# Sec_Gate_Driver.net
KiCad netlist of a schematic drawn in Altium Designer
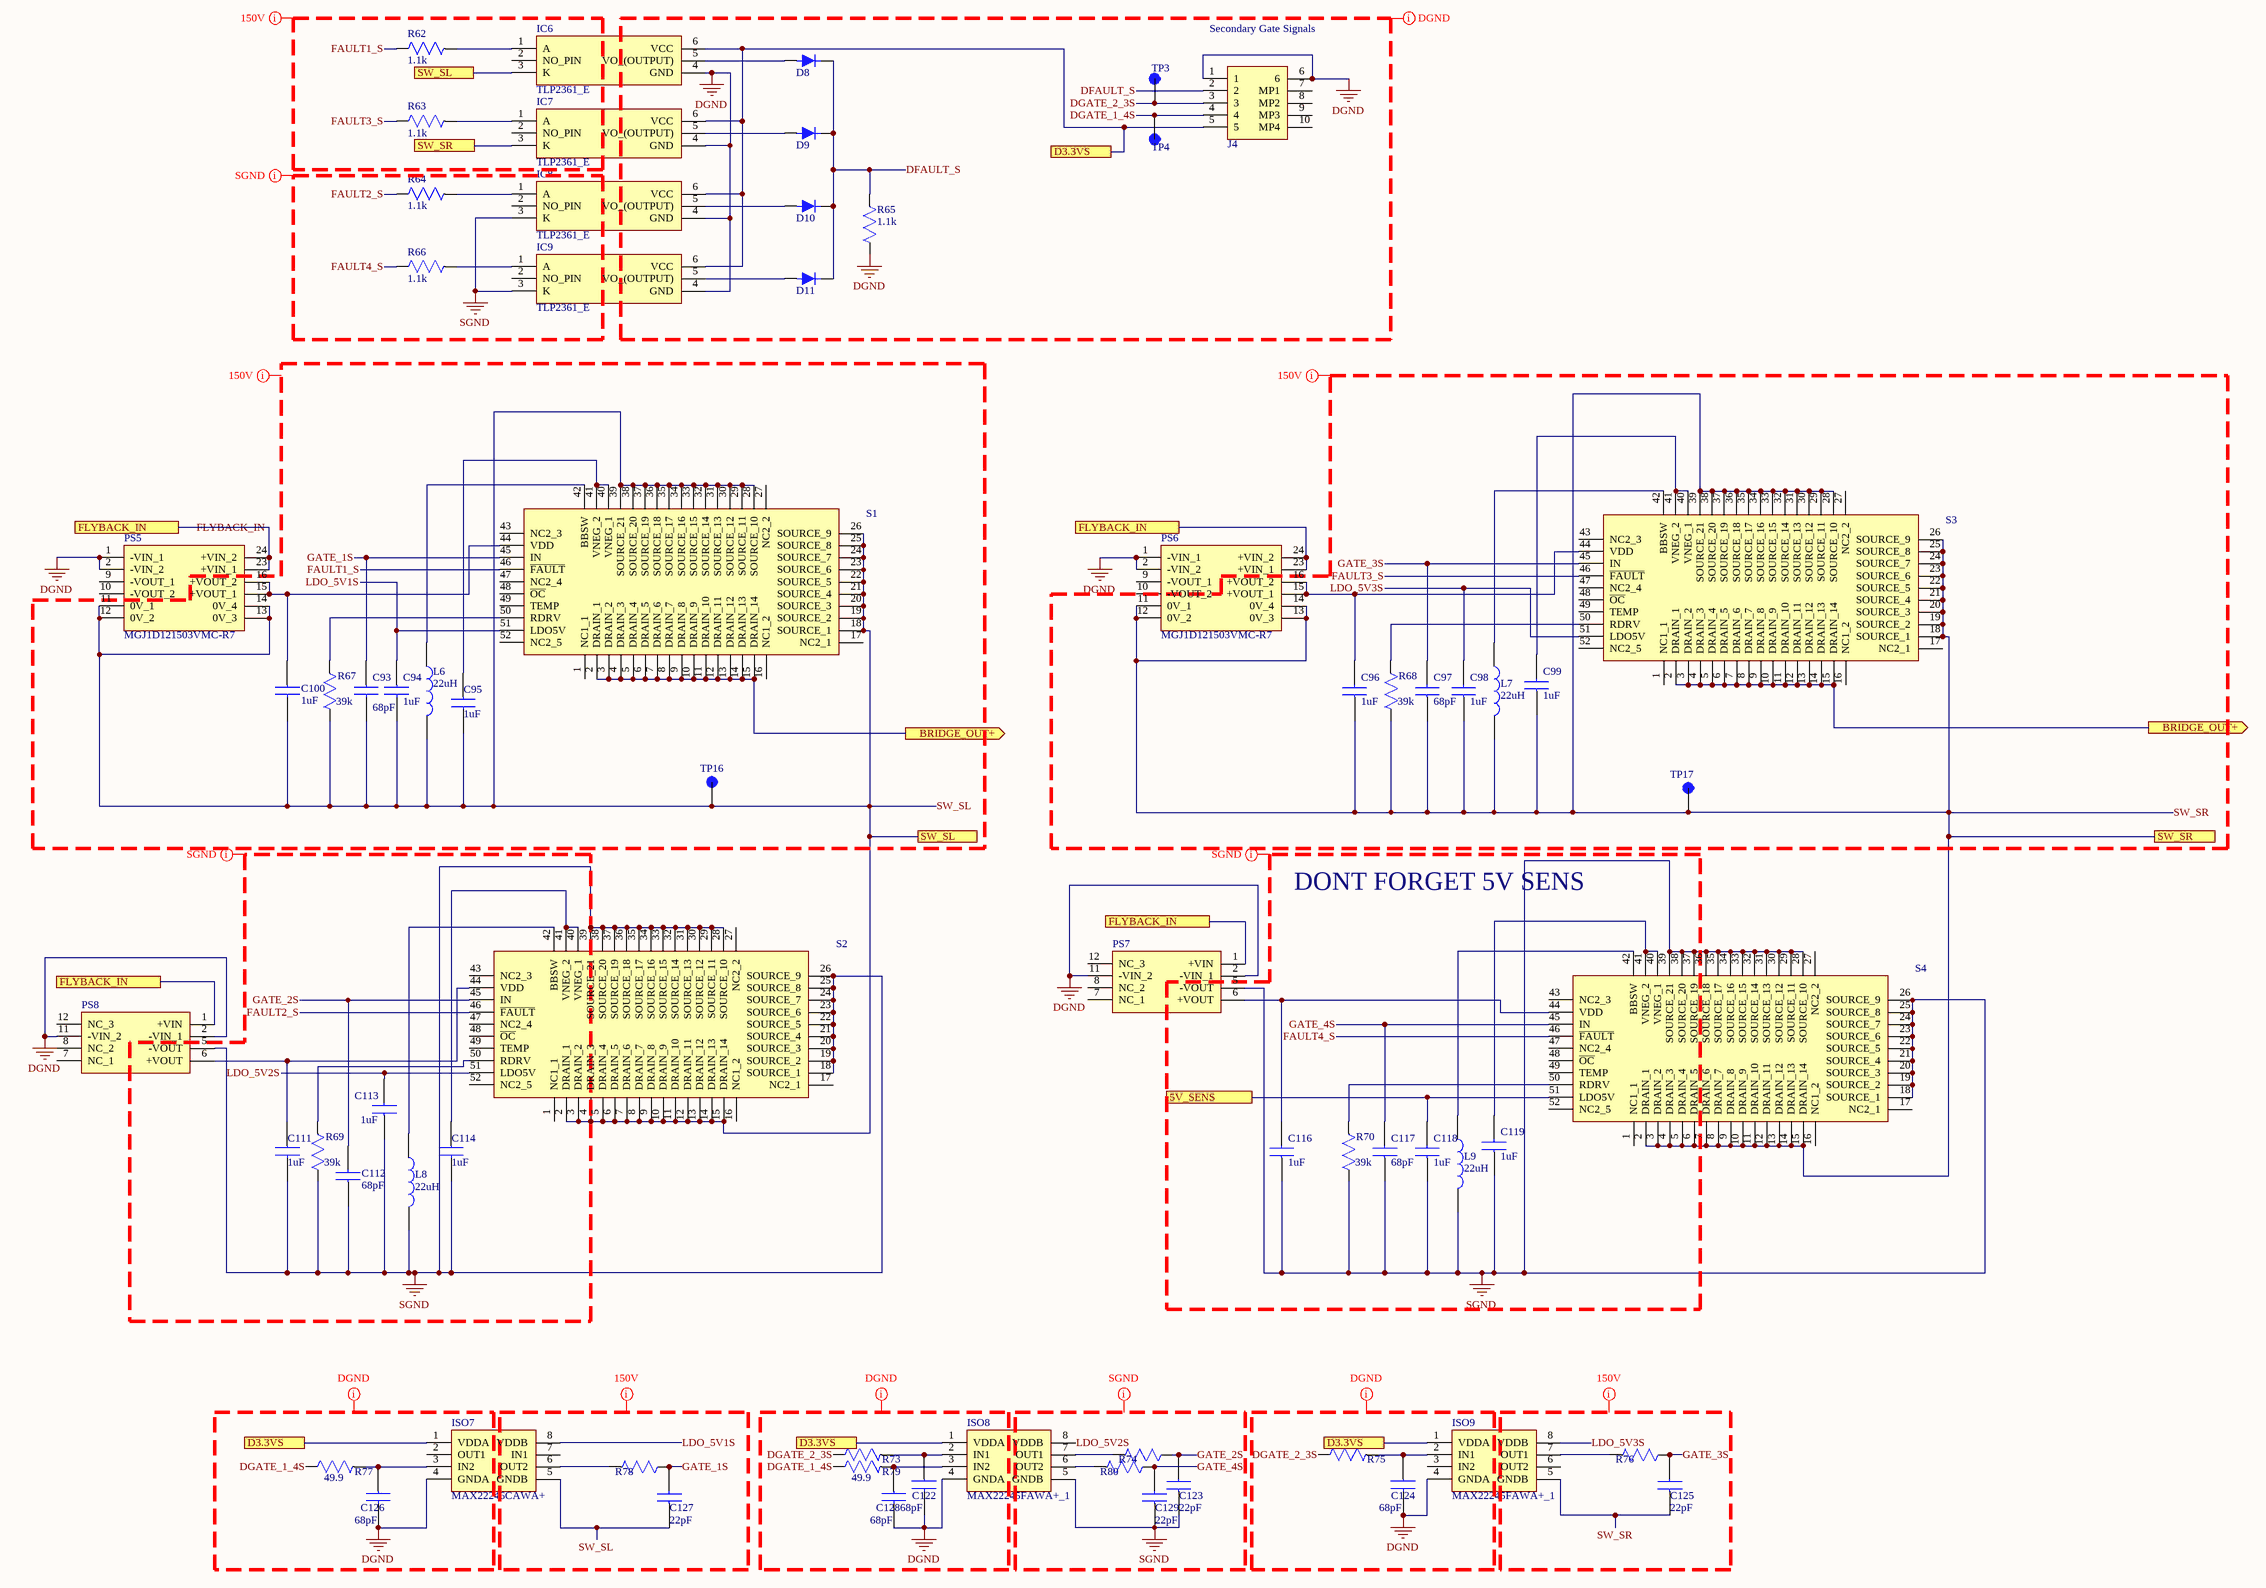
[diagram p0: Sec_Gate_Driver.SchDoc]

(export (version "E")
  (design (tool "Eeschema 10.0.6"))
  (components
    (comp (ref "C93")
      (value "68pF")
      (footprint "C0805")
      (description "Capacitor")
      (fields
        (field (name "MANUFACTURER_PART_NUMBER") "C0805C680J5GACTU")
        (field (name "MOUSER PART NUMBER") "80-C0805C680J5G")
      )
      (libsource (lib "PriGateDriver") (part "C0805C680J5GACTU"))
    )
    (comp (ref "C94")
      (value "1uF")
      (footprint "CAPC2012X135N")
      (description "Capacitor")
      (fields
        (field (name "MANUFACTURER_PART_NUMBER") "CL21B105KBFNNNE")
        (field (name "MOUSER PART NUMBER") "187-CL21B105KBFNNNE")
      )
      (libsource (lib "SecGateDriver") (part "CL21B105KBFNNNE"))
    )
    (comp (ref "C95")
      (value "1uF")
      (footprint "CAPC2012X135N")
      (description "Capacitor")
      (fields
        (field (name "MANUFACTURER_PART_NUMBER") "CL21B105KBFNNNE")
        (field (name "MOUSER PART NUMBER") "187-CL21B105KBFNNNE")
      )
      (libsource (lib "SecGateDriver") (part "CL21B105KBFNNNE"))
    )
    (comp (ref "C96")
      (value "1uF")
      (footprint "CAPC2012X70N")
      (description "CAP CER 1UF 50V X7R 0805")
      (fields
        (field (name "MANUFACTURER_PART_NUMBER") "CL21B105KBFNNNE")
        (field (name "MOUSER PART NUMBER") "187-CL21B105KBFNNNE")
      )
      (libsource (lib "SecGateDriver") (part "CL21B105KBFNNNE"))
    )
    (comp (ref "C97")
      (value "68pF")
      (footprint "C0805")
      (description "CAP CER 68PF 50V C0G/NP0 0805")
      (fields
        (field (name "MANUFACTURER_PART_NUMBER") "C0805C680J5GACTU")
        (field (name "MOUSER PART NUMBER") "80-C0805C680J5G")
      )
      (libsource (lib "SecGateDriver") (part "C0805C680J5GACTU"))
    )
    (comp (ref "C98")
      (value "1uF")
      (footprint "CAPC2012X135N")
      (description "CAP CER 1UF 50V X7R 0805")
      (fields
        (field (name "MANUFACTURER_PART_NUMBER") "CL21B105KBFNNNE")
        (field (name "MOUSER PART NUMBER") "187-CL21B105KBFNNNE")
      )
      (libsource (lib "SecGateDriver") (part "CL21B105KBFNNNE"))
    )
    (comp (ref "C99")
      (value "1uF")
      (footprint "CAPC2012X135N")
      (description "CAP CER 1UF 50V X7R 0805")
      (fields
        (field (name "MANUFACTURER_PART_NUMBER") "CL21B105KBFNNNE")
        (field (name "MOUSER PART NUMBER") "187-CL21B105KBFNNNE")
      )
      (libsource (lib "SecGateDriver") (part "CL21B105KBFNNNE"))
    )
    (comp (ref "C100")
      (value "1uF")
      (footprint "CAPC2012X135N")
      (description "Capacitor")
      (fields
        (field (name "MANUFACTURER_PART_NUMBER") "CL21B105KBFNNNE")
        (field (name "MOUSER PART NUMBER") "187-CL21B105KBFNNNE")
      )
      (libsource (lib "SecGateDriver") (part "CL21B105KBFNNNE"))
    )
    (comp (ref "C111")
      (value "1uF")
      (footprint "CAPC2012X135N")
      (description "Capacitor")
      (fields
        (field (name "MANUFACTURER_PART_NUMBER") "CL21B105KBFNNNE")
        (field (name "MOUSER PART NUMBER") "187-CL21B105KBFNNNE")
      )
      (libsource (lib "SecGateDriver") (part "CL21B105KBFNNNE"))
    )
    (comp (ref "C112")
      (value "68pF")
      (footprint "C0805")
      (description "CAP CER 68PF 50V C0G/NP0 0805")
      (fields
        (field (name "MANUFACTURER_PART_NUMBER") "C0805C680J5GACTU")
        (field (name "MOUSER PART NUMBER") "80-C0805C680J5G")
      )
      (libsource (lib "Sec_Gate_Driver") (part "C0805C680J5GACTU_1"))
    )
    (comp (ref "C113")
      (value "1uF")
      (footprint "CAPC2012X70N")
      (description "CAP CER 1UF 50V X7R 0805")
      (fields
        (field (name "MANUFACTURER_PART_NUMBER") "CL21B105KBFNNNE")
        (field (name "MOUSER PART NUMBER") "187-CL21B105KBFNNNE")
      )
      (libsource (lib "Sec_Gate_Driver") (part "CL21B105KBFNNNE"))
    )
    (comp (ref "C114")
      (value "1uF")
      (footprint "CAPC2012X135N")
      (description "Capacitor")
      (fields
        (field (name "MANUFACTURER_PART_NUMBER") "CL21B105KBFNNNE")
        (field (name "MOUSER PART NUMBER") "187-CL21B105KBFNNNE")
      )
      (libsource (lib "SecGateDriver") (part "CL21B105KBFNNNE"))
    )
    (comp (ref "C116")
      (value "1uF")
      (footprint "CAPC2012X70N")
      (description "CAP CER 1UF 50V X7R 0805")
      (fields
        (field (name "MANUFACTURER_PART_NUMBER") "CL21B105KBFNNNE")
        (field (name "MOUSER PART NUMBER") "187-CL21B105KBFNNNE")
      )
      (libsource (lib "SecGateDriver") (part "CL21B105KBFNNNE"))
    )
    (comp (ref "C117")
      (value "68pF")
      (footprint "C0805")
      (description "CAP CER 68PF 50V C0G/NP0 0805")
      (fields
        (field (name "MANUFACTURER_PART_NUMBER") "C0805C680J5GACTU")
        (field (name "MOUSER PART NUMBER") "80-C0805C680J5G")
      )
      (libsource (lib "SecGateDriver") (part "C0805C680J5GACTU"))
    )
    (comp (ref "C118")
      (value "1uF")
      (footprint "CAPC2012X70N")
      (description "CAP CER 1UF 50V X7R 0805")
      (fields
        (field (name "MANUFACTURER_PART_NUMBER") "CL21B105KBFNNNE")
        (field (name "MOUSER PART NUMBER") "187-CL21B105KBFNNNE")
      )
      (libsource (lib "SecGateDriver") (part "CL21B105KBFNNNE"))
    )
    (comp (ref "C119")
      (value "1uF")
      (footprint "CAPC2012X70N")
      (description "CAP CER 1UF 50V X7R 0805")
      (fields
        (field (name "MANUFACTURER_PART_NUMBER") "CL21B105KBFNNNE")
        (field (name "MOUSER PART NUMBER") "187-CL21B105KBFNNNE")
      )
      (libsource (lib "SecGateDriver") (part "CL21B105KBFNNNE"))
    )
    (comp (ref "C122")
      (value "68pF")
      (footprint "C0805")
      (description "CAP CER 68PF 50V C0G/NP0 0805")
      (fields
        (field (name "MANUFACTURER_PART_NUMBER") "C0805C680J5GACTU")
        (field (name "MOUSER PART NUMBER") "80-C0805C680J5G")
      )
      (libsource (lib "Sec_Gate_Driver") (part "C0805C680J5GACTU_1"))
    )
    (comp (ref "C123")
      (value "22pF")
      (footprint "C0805")
      (description "CAP CER 22PF 100V C0G/NP0 0805")
      (fields
        (field (name "MANUFACTURER_PART_NUMBER") "C0805C220J1GACTU")
        (field (name "MOUSER PART NUMBER") "80-C0805C220J1G")
      )
      (libsource (lib "Sec_Gate_Driver") (part "C0805C220J1GACTU"))
    )
    (comp (ref "C124")
      (value "68pF")
      (footprint "C0805")
      (description "CAP CER 68PF 50V C0G/NP0 0805")
      (fields
        (field (name "MANUFACTURER_PART_NUMBER") "C0805C680J5GACTU")
        (field (name "MOUSER PART NUMBER") "80-C0805C680J5G")
      )
      (libsource (lib "Sec_Gate_Driver") (part "C0805C680J5GACTU_1"))
    )
    (comp (ref "C125")
      (value "22pF")
      (footprint "C0805")
      (description "CAP CER 22PF 100V C0G/NP0 0805")
      (fields
        (field (name "MANUFACTURER_PART_NUMBER") "C0805C220J1GACTU")
        (field (name "MOUSER PART NUMBER") "80-C0805C220J1G")
      )
      (libsource (lib "Sec_Gate_Driver") (part "C0805C220J1GACTU"))
    )
    (comp (ref "C126")
      (value "68pF")
      (footprint "C0805")
      (description "CAP CER 68PF 50V C0G/NP0 0805")
      (fields
        (field (name "MANUFACTURER_PART_NUMBER") "C0805C680J5GACTU")
        (field (name "MOUSER PART NUMBER") "80-C0805C680J5G")
      )
      (libsource (lib "Sec_Gate_Driver") (part "C0805C680J5GACTU_1"))
    )
    (comp (ref "C127")
      (value "22pF")
      (footprint "C0805")
      (description "CAP CER 22PF 100V C0G/NP0 0805")
      (fields
        (field (name "MANUFACTURER_PART_NUMBER") "C0805C220J1GACTU")
        (field (name "MOUSER PART NUMBER") "80-C0805C220J1G")
      )
      (libsource (lib "Sec_Gate_Driver") (part "C0805C220J1GACTU"))
    )
    (comp (ref "C128")
      (value "68pF")
      (footprint "C0805")
      (description "CAP CER 68PF 50V C0G/NP0 0805")
      (fields
        (field (name "MANUFACTURER_PART_NUMBER") "C0805C680J5GACTU")
        (field (name "MOUSER PART NUMBER") "80-C0805C680J5G")
      )
      (libsource (lib "Sec_Gate_Driver") (part "C0805C680J5GACTU_1"))
    )
    (comp (ref "C129")
      (value "22pF")
      (footprint "C0805")
      (description "CAP CER 22PF 100V C0G/NP0 0805")
      (fields
        (field (name "MANUFACTURER_PART_NUMBER") "C0805C220J1GACTU")
        (field (name "MOUSER PART NUMBER") "80-C0805C220J1G")
      )
      (libsource (lib "Sec_Gate_Driver") (part "C0805C220J1GACTU"))
    )
    (comp (ref "D8")
      (value "CUS520,H3F")
      (footprint "SOD2513X115N")
      (description "DIODE SCHOTTKY 30V 200MA USC")
      (fields
        (field (name "MANUFACTURER_PART_NUMBER") "MMSD4148T1G")
        (field (name "MOUSER PART NUMBER") "863-MMSD4148T1G")
      )
      (libsource (lib "Sec_Gate_Driver") (part "CUS520,H3F"))
    )
    (comp (ref "D9")
      (value "CUS520,H3F")
      (footprint "SOD2513X115N")
      (description "DIODE SCHOTTKY 30V 200MA USC")
      (fields
        (field (name "MANUFACTURER_PART_NUMBER") "MMSD4148T1G")
        (field (name "MOUSER PART NUMBER") "863-MMSD4148T1G")
      )
      (libsource (lib "Sec_Gate_Driver") (part "CUS520,H3F"))
    )
    (comp (ref "D10")
      (value "CUS520,H3F")
      (footprint "SOD2513X115N")
      (description "DIODE SCHOTTKY 30V 200MA USC")
      (fields
        (field (name "MANUFACTURER_PART_NUMBER") "MMSD4148T1G")
        (field (name "MOUSER PART NUMBER") "863-MMSD4148T1G")
      )
      (libsource (lib "Sec_Gate_Driver") (part "CUS520,H3F"))
    )
    (comp (ref "D11")
      (value "CUS520,H3F")
      (footprint "SOD2513X115N")
      (description "DIODE SCHOTTKY 30V 200MA USC")
      (fields
        (field (name "MANUFACTURER_PART_NUMBER") "MMSD4148T1G")
        (field (name "MOUSER PART NUMBER") "863-MMSD4148T1G")
      )
      (libsource (lib "Sec_Gate_Driver") (part "CUS520,H3F"))
    )
    (comp (ref "IC6")
      (value "TLP2361_E")
      (footprint "SOIC127P700X230-6N")
      (description "Integrated Circuit")
      (fields
        (field (name "MANUFACTURER_PART_NUMBER") "TLP2361(E")
        (field (name "MOUSER PART NUMBER") "757-TLP2361(E")
      )
      (libsource (lib "Sec_Gate_Driver") (part "TLP2361_E"))
    )
    (comp (ref "IC7")
      (value "TLP2361_E")
      (footprint "SOIC127P700X230-6N")
      (description "Integrated Circuit")
      (fields
        (field (name "MANUFACTURER_PART_NUMBER") "TLP2361(E")
        (field (name "MOUSER PART NUMBER") "757-TLP2361(E")
      )
      (libsource (lib "Sec_Gate_Driver") (part "TLP2361_E"))
    )
    (comp (ref "IC8")
      (value "TLP2361_E")
      (footprint "SOIC127P700X230-6N")
      (description "Integrated Circuit")
      (fields
        (field (name "MANUFACTURER_PART_NUMBER") "TLP2361(E")
        (field (name "MOUSER PART NUMBER") "757-TLP2361(E")
      )
      (libsource (lib "Sec_Gate_Driver") (part "TLP2361_E"))
    )
    (comp (ref "IC9")
      (value "TLP2361_E")
      (footprint "SOIC127P700X230-6N")
      (description "Integrated Circuit")
      (fields
        (field (name "MANUFACTURER_PART_NUMBER") "TLP2361(E")
        (field (name "MOUSER PART NUMBER") "757-TLP2361(E")
      )
      (libsource (lib "Sec_Gate_Driver") (part "TLP2361_E"))
    )
    (comp (ref "ISO7")
      (value "MAX22246CAWA+")
      (footprint "SOIC127P1031X265-8N")
      (description "DG ISO 5KV 2CH CAN/RS232 8-SOIC")
      (fields (field (name "MOUSER PART NUMBER") "700-MAX22246CAWA+"))
      (libsource (lib "Sec_Gate_Driver") (part "MAX22246CAWA+"))
    )
    (comp (ref "ISO8")
      (value "MAX22245FAWA+_1")
      (footprint "SOIC127P1031X265-8N")
      (description "DG ISO 5KV 2CH CAN/RS232 8-SOIC")
      (fields (field (name "MANUFACTURER_PART_NUMBER") "MAX22245FAWA+"))
      (libsource (lib "Sec_Gate_Driver") (part "MAX22245FAWA+_1"))
    )
    (comp (ref "ISO9")
      (value "MAX22245FAWA+_1")
      (footprint "SOIC127P1031X265-8N")
      (description "DG ISO 5KV 2CH CAN/RS232 8-SOIC")
      (fields (field (name "MANUFACTURER_PART_NUMBER") "MAX22245FAWA+"))
      (libsource (lib "Sec_Gate_Driver") (part "MAX22245FAWA+_1"))
    )
    (comp (ref "J4")
      (value "0527450696")
      (footprint "0527450696")
      (description "CONN FFC FPC TOP 6POS 0.5MM R/A")
      (libsource (lib "Sec_Gate_Driver") (part "0527450696"))
    )
    (comp (ref "L6")
      (value "22uH")
      (footprint "LQM21DN220N00L")
      (description "Inductor")
      (fields
        (field (name "MANUFACTURER_PART_NUMBER") "LQM21DH220M70L")
        (field (name "MOUSER PART NUMBER") "81-LQM21DH220M70L")
      )
      (libsource (lib "SecGateDriver") (part "LQM21DH220M70L"))
    )
    (comp (ref "L7")
      (value "22uH")
      (footprint "LQM21DN220N00L")
      (description "FIXED IND 22UH 220MA 1.625OHM SM")
      (fields
        (field (name "MANUFACTURER_PART_NUMBER") "LQM21DH220M70L")
        (field (name "MOUSER PART NUMBER") "81-LQM21DH220M70L")
      )
      (libsource (lib "SecGateDriver") (part "LQM21DH220M70L"))
    )
    (comp (ref "L8")
      (value "22uH")
      (footprint "LQM21DN220N00L")
      (description "Inductor")
      (fields
        (field (name "MANUFACTURER_PART_NUMBER") "LQM21DH220M70L")
        (field (name "MOUSER PART NUMBER") "81-LQM21DH220M70L")
      )
      (libsource (lib "SecGateDriver") (part "LQM21DH220M70L"))
    )
    (comp (ref "L9")
      (value "22uH")
      (footprint "LQM21DN220N00L")
      (description "FIXED IND 22UH 220MA 1.625OHM SM")
      (fields
        (field (name "MANUFACTURER_PART_NUMBER") "LQM21DH220M70L")
        (field (name "MOUSER PART NUMBER") "81-LQM21DH220M70L")
      )
      (libsource (lib "SecGateDriver") (part "LQM21DH220M70L"))
    )
    (comp (ref "PS5")
      (value "MGJ1D121503VMC-R7")
      (footprint "MGJ1D121503VMCR7")
      (description "DC DC CONVERTER 15V -3V 1W")
      (fields (field (name "MOUSER PART NUMBER") "580-MGJ1D121503VMCR7"))
      (libsource (lib "SecGateDriver") (part "MGJ1D121503VMC-R7"))
    )
    (comp (ref "PS6")
      (value "MGJ1D121503VMC-R7")
      (footprint "MGJ1D121503VMCR7")
      (description "DC DC CONVERTER 15V -3V 1W")
      (fields (field (name "MOUSER PART NUMBER") "580-MGJ1D121503VMCR7"))
      (libsource (lib "SecGateDriver") (part "MGJ1D121503VMC-R7"))
    )
    (comp (ref "PS7")
      (value "NXJ2S1212MC-R7")
      (footprint "NXJ2S1212MCR7")
      (description "DC DC CONVERTER 12V 2W")
      (fields (field (name "MOUSER PART NUMBER") "580-NXJ2S1212MC-R7"))
      (libsource (lib "Sec_Gate_Driver") (part "NXJ2S1212MC-R7"))
    )
    (comp (ref "PS8")
      (value "NXJ2S1212MC-R7")
      (footprint "NXJ2S1212MCR7")
      (description "DC DC CONVERTER 12V 2W")
      (fields (field (name "MOUSER PART NUMBER") "580-NXJ2S1212MC-R7"))
      (libsource (lib "SecGateDriver") (part "NXJ2S1212MC-R7"))
    )
    (comp (ref "R62")
      (value "1.1k")
      (footprint "RESC2012X60N")
      (description "RES 1.1K OHM 5% 1/8W 0805")
      (fields
        (field (name "MANUFACTURER_PART_NUMBER") "ERJ-PB6B1002V")
        (field (name "MOUSER PART NUMBER") "667-ERJ-PB6B1002V")
      )
      (libsource (lib "Sec_Gate_Driver") (part "RMCF0805JT1K10"))
    )
    (comp (ref "R63")
      (value "1.1k")
      (footprint "RESC2012X60N")
      (description "RES 1.1K OHM 5% 1/8W 0805")
      (fields
        (field (name "MANUFACTURER_PART_NUMBER") "ERJ-PB6B1002V")
        (field (name "MOUSER PART NUMBER") "667-ERJ-PB6B1002V")
      )
      (libsource (lib "Sec_Gate_Driver") (part "RMCF0805JT1K10"))
    )
    (comp (ref "R64")
      (value "1.1k")
      (footprint "RESC2012X60N")
      (description "RES 1.1K OHM 5% 1/8W 0805")
      (fields
        (field (name "MANUFACTURER_PART_NUMBER") "ERJ-PB6B1002V")
        (field (name "MOUSER PART NUMBER") "667-ERJ-PB6B1002V")
      )
      (libsource (lib "Sec_Gate_Driver") (part "RMCF0805JT1K10"))
    )
    (comp (ref "R65")
      (value "1.1k")
      (footprint "RESC2012X60N")
      (description "RES 1.1K OHM 5% 1/8W 0805")
      (fields
        (field (name "MANUFACTURER_PART_NUMBER") "ERJ-PB6B1002V")
        (field (name "MOUSER PART NUMBER") "667-ERJ-PB6B1002V")
      )
      (libsource (lib "Sec_Gate_Driver") (part "RMCF0805JT1K10"))
    )
    (comp (ref "R66")
      (value "1.1k")
      (footprint "RESC2012X60N")
      (description "RES 1.1K OHM 5% 1/8W 0805")
      (fields
        (field (name "MANUFACTURER_PART_NUMBER") "ERJ-PB6B1002V")
        (field (name "MOUSER PART NUMBER") "667-ERJ-PB6B1002V")
      )
      (libsource (lib "Sec_Gate_Driver") (part "RMCF0805JT1K10"))
    )
    (comp (ref "R67")
      (value "39k")
      (footprint "C0805")
      (description "39 kOhms ±0.1% 0.25W, 1/4W Chip Resistor 0805 (2012 Metric) Automotive AEC-Q200 Thick Film")
      (fields (field (name "MANUFACTURER_PART_NUMBER") "RC0603JR0710KL"))
      (libsource (lib "SecGateDriver") (part "ERJ-PB6B3902V"))
    )
    (comp (ref "R68")
      (value "39k")
      (footprint "C0805")
      (description "39 kOhms ±0.1% 0.25W, 1/4W Chip Resistor 0805 (2012 Metric) Automotive AEC-Q200 Thick Film")
      (fields (field (name "MANUFACTURER_PART_NUMBER") "RC0603JR0710KL"))
      (libsource (lib "SecGateDriver") (part "ERJ-PB6B3902V"))
    )
    (comp (ref "R69")
      (value "39k")
      (footprint "ERJP06D1000V")
      (description "39 kOhms ±0.1% 0.25W, 1/4W Chip Resistor 0805 (2012 Metric) Automotive AEC-Q200 Thick Film")
      (fields (field (name "MANUFACTURER_PART_NUMBER") "RC0603JR0710KL"))
      (libsource (lib "SecGateDriver") (part "ERJ-PB6B3902V"))
    )
    (comp (ref "R70")
      (value "39k")
      (footprint "C0805")
      (description "39 kOhms ±0.1% 0.25W, 1/4W Chip Resistor 0805 (2012 Metric) Automotive AEC-Q200 Thick Film")
      (fields (field (name "MANUFACTURER_PART_NUMBER") "RC0603JR0710KL"))
      (libsource (lib "SecGateDriver") (part "ERJ-PB6B3902V"))
    )
    (comp (ref "R73")
      (value "49.9")
      (footprint "RESC2013X84N")
      (description "RES SMD 49.9 OHM 0.1% 1W 0805")
      (fields
        (field (name "MANUFACTURER_PART_NUMBER") "PCAN0805E49R9BST5")
        (field (name "MOUSER PART NUMBER") "71-PCAN0805E49R9BST5")
      )
      (libsource (lib "Sec_Gate_Driver") (part "PCAN0805E49R9BST5"))
    )
    (comp (ref "R74")
      (value "49.9")
      (footprint "RESC2013X84N")
      (description "RES SMD 49.9 OHM 0.1% 1W 0805")
      (fields
        (field (name "MANUFACTURER_PART_NUMBER") "PCAN0805E49R9BST5")
        (field (name "MOUSER PART NUMBER") "71-PCAN0805E49R9BST5")
      )
      (libsource (lib "Sec_Gate_Driver") (part "PCAN0805E49R9BST5"))
    )
    (comp (ref "R75")
      (value "49.9")
      (footprint "RESC2013X84N")
      (description "RES SMD 49.9 OHM 0.1% 1W 0805")
      (fields
        (field (name "MANUFACTURER_PART_NUMBER") "PCAN0805E49R9BST5")
        (field (name "MOUSER PART NUMBER") "71-PCAN0805E49R9BST5")
      )
      (libsource (lib "Sec_Gate_Driver") (part "PCAN0805E49R9BST5"))
    )
    (comp (ref "R76")
      (value "49.9")
      (footprint "RESC2013X84N")
      (description "RES SMD 49.9 OHM 0.1% 1W 0805")
      (fields
        (field (name "MANUFACTURER_PART_NUMBER") "PCAN0805E49R9BST5")
        (field (name "MOUSER PART NUMBER") "71-PCAN0805E49R9BST5")
      )
      (libsource (lib "Sec_Gate_Driver") (part "PCAN0805E49R9BST5"))
    )
    (comp (ref "R77")
      (value "49.9")
      (footprint "RESC2013X84N")
      (description "RES SMD 49.9 OHM 0.1% 1W 0805")
      (fields
        (field (name "MANUFACTURER_PART_NUMBER") "PCAN0805E49R9BST5")
        (field (name "MOUSER PART NUMBER") "71-PCAN0805E49R9BST5")
      )
      (libsource (lib "Sec_Gate_Driver") (part "PCAN0805E49R9BST5"))
    )
    (comp (ref "R78")
      (value "49.9")
      (footprint "RESC2013X84N")
      (description "RES SMD 49.9 OHM 0.1% 1W 0805")
      (fields
        (field (name "MANUFACTURER_PART_NUMBER") "PCAN0805E49R9BST5")
        (field (name "MOUSER PART NUMBER") "71-PCAN0805E49R9BST5")
      )
      (libsource (lib "Sec_Gate_Driver") (part "PCAN0805E49R9BST5"))
    )
    (comp (ref "R79")
      (value "49.9")
      (footprint "RESC2013X84N")
      (description "RES SMD 49.9 OHM 0.1% 1W 0805")
      (fields
        (field (name "MANUFACTURER_PART_NUMBER") "PCAN0805E49R9BST5")
        (field (name "MOUSER PART NUMBER") "71-PCAN0805E49R9BST5")
      )
      (libsource (lib "Sec_Gate_Driver") (part "PCAN0805E49R9BST5"))
    )
    (comp (ref "R80")
      (value "49.9")
      (footprint "RESC2013X84N")
      (description "RES SMD 49.9 OHM 0.1% 1W 0805")
      (fields
        (field (name "MANUFACTURER_PART_NUMBER") "PCAN0805E49R9BST5")
        (field (name "MOUSER PART NUMBER") "71-PCAN0805E49R9BST5")
      )
      (libsource (lib "Sec_Gate_Driver") (part "PCAN0805E49R9BST5"))
    )
    (comp (ref "S1")
      (value "LMG3522R030RQSR")
      (footprint "LMG3522R050RQSR")
      (description "Integrated Circuit")
      (fields
        (field (name "MANUFACTURER_PART_NUMBER") "LMG3522R050RQSR")
        (field (name "MOUSER PART NUMBER") "595-LMG3522R050RQSR")
      )
      (libsource (lib "*") (part "LMG3522R050RQSR"))
    )
    (comp (ref "S2")
      (value "LMG3522R030RQSR")
      (footprint "LMG3522R050RQSR")
      (description "Integrated Circuit")
      (fields
        (field (name "MANUFACTURER_PART_NUMBER") "LMG3522R050RQSR")
        (field (name "MOUSER PART NUMBER") "595-LMG3522R050RQSR")
      )
      (libsource (lib "*") (part "LMG3522R050RQSR"))
    )
    (comp (ref "S3")
      (value "LMG3522R030RQSR")
      (footprint "LMG3522R050RQSR")
      (description "Integrated Circuit")
      (fields
        (field (name "MANUFACTURER_PART_NUMBER") "LMG3522R050RQSR")
        (field (name "MOUSER PART NUMBER") "595-LMG3522R050RQSR")
      )
      (libsource (lib "*") (part "LMG3522R050RQSR"))
    )
    (comp (ref "S4")
      (value "LMG3522R030RQSR")
      (footprint "LMG3522R050RQSR")
      (description "Integrated Circuit")
      (fields
        (field (name "MANUFACTURER_PART_NUMBER") "LMG3522R050RQSR")
        (field (name "MOUSER PART NUMBER") "595-LMG3522R050RQSR")
      )
      (libsource (lib "*") (part "LMG3522R050RQSR"))
    )
    (comp (ref "TP3")
      (value "Test Point 5011")
      (footprint "TP_5011")
      (fields (field (name "MP") "altium_native_batch"))
      (libsource (lib "Sec_Gate_Driver") (part "Test Point 5011"))
    )
    (comp (ref "TP4")
      (value "Test Point 5011")
      (footprint "TP_5011")
      (fields (field (name "MP") "altium_native_batch"))
      (libsource (lib "Sec_Gate_Driver") (part "Test Point 5011"))
    )
    (comp (ref "TP16")
      (value "Secondary Switch Node Left")
      (footprint "TP_5011")
      (description "Test Point 5011")
      (fields (field (name "MP") "altium_native_batch"))
      (libsource (lib "Sec_Gate_Driver") (part "Test Point 5011"))
    )
    (comp (ref "TP17")
      (value "Switch Node Secondary Right")
      (footprint "TP_5011")
      (description "Test Point 5011")
      (fields (field (name "MP") "altium_native_batch"))
      (libsource (lib "Sec_Gate_Driver") (part "Test Point 5011"))
    )
  )
  (nets
    (net (code "1") (name "/5V_SENS") (class "Default")
      (node (ref "C118") (pin "2") (pinfunction "2_2") (pintype "passive"))
      (node (ref "S4") (pin "51") (pinfunction "LDO5V_51") (pintype "passive"))
    )
    (net (code "2") (name "/BRIDGE_OUT+") (class "Default")
      (node (ref "S1") (pin "10") (pinfunction "DRAIN_9_10") (pintype "passive"))
      (node (ref "S1") (pin "11") (pinfunction "DRAIN_10_11") (pintype "passive"))
      (node (ref "S1") (pin "12") (pinfunction "DRAIN_11_12") (pintype "passive"))
      (node (ref "S1") (pin "13") (pinfunction "DRAIN_12_13") (pintype "passive"))
      (node (ref "S1") (pin "14") (pinfunction "DRAIN_13_14") (pintype "passive"))
      (node (ref "S1") (pin "15") (pinfunction "DRAIN_14_15") (pintype "passive"))
      (node (ref "S1") (pin "2") (pinfunction "DRAIN_1_2") (pintype "passive"))
      (node (ref "S1") (pin "3") (pinfunction "DRAIN_2_3") (pintype "passive"))
      (node (ref "S1") (pin "4") (pinfunction "DRAIN_3_4") (pintype "passive"))
      (node (ref "S1") (pin "5") (pinfunction "DRAIN_4_5") (pintype "passive"))
      (node (ref "S1") (pin "6") (pinfunction "DRAIN_5_6") (pintype "passive"))
      (node (ref "S1") (pin "7") (pinfunction "DRAIN_6_7") (pintype "passive"))
      (node (ref "S1") (pin "8") (pinfunction "DRAIN_7_8") (pintype "passive"))
      (node (ref "S1") (pin "9") (pinfunction "DRAIN_8_9") (pintype "passive"))
      (node (ref "S3") (pin "10") (pinfunction "DRAIN_9_10") (pintype "passive"))
      (node (ref "S3") (pin "11") (pinfunction "DRAIN_10_11") (pintype "passive"))
      (node (ref "S3") (pin "12") (pinfunction "DRAIN_11_12") (pintype "passive"))
      (node (ref "S3") (pin "13") (pinfunction "DRAIN_12_13") (pintype "passive"))
      (node (ref "S3") (pin "14") (pinfunction "DRAIN_13_14") (pintype "passive"))
      (node (ref "S3") (pin "15") (pinfunction "DRAIN_14_15") (pintype "passive"))
      (node (ref "S3") (pin "2") (pinfunction "DRAIN_1_2") (pintype "passive"))
      (node (ref "S3") (pin "3") (pinfunction "DRAIN_2_3") (pintype "passive"))
      (node (ref "S3") (pin "4") (pinfunction "DRAIN_3_4") (pintype "passive"))
      (node (ref "S3") (pin "5") (pinfunction "DRAIN_4_5") (pintype "passive"))
      (node (ref "S3") (pin "6") (pinfunction "DRAIN_5_6") (pintype "passive"))
      (node (ref "S3") (pin "7") (pinfunction "DRAIN_6_7") (pintype "passive"))
      (node (ref "S3") (pin "8") (pinfunction "DRAIN_7_8") (pintype "passive"))
      (node (ref "S3") (pin "9") (pinfunction "DRAIN_8_9") (pintype "passive"))
    )
    (net (code "3") (name "/D3.3VS") (class "Default")
      (node (ref "IC6") (pin "6") (pinfunction "VCC_6") (pintype "passive"))
      (node (ref "IC7") (pin "6") (pinfunction "VCC_6") (pintype "passive"))
      (node (ref "IC8") (pin "6") (pinfunction "VCC_6") (pintype "passive"))
      (node (ref "IC9") (pin "6") (pinfunction "VCC_6") (pintype "passive"))
      (node (ref "ISO7") (pin "1") (pinfunction "VDDA_1") (pintype "passive"))
      (node (ref "ISO8") (pin "1") (pinfunction "VDDA_1") (pintype "passive"))
      (node (ref "ISO9") (pin "1") (pinfunction "VDDA_1") (pintype "passive"))
      (node (ref "J4") (pin "5") (pinfunction "5_5") (pintype "passive"))
    )
    (net (code "4") (name "/DFAULT_S") (class "Default")
      (node (ref "D10") (pin "2") (pinfunction "2_2") (pintype "passive"))
      (node (ref "D11") (pin "2") (pinfunction "2_2") (pintype "passive"))
      (node (ref "D8") (pin "2") (pinfunction "2_2") (pintype "passive"))
      (node (ref "D9") (pin "2") (pinfunction "2_2") (pintype "passive"))
      (node (ref "J4") (pin "2") (pinfunction "2_2") (pintype "passive"))
      (node (ref "R65") (pin "2") (pinfunction "2_2") (pintype "passive"))
    )
    (net (code "5") (name "/DGATE_1_4S") (class "Default")
      (node (ref "J4") (pin "4") (pinfunction "4_4") (pintype "passive"))
      (node (ref "R77") (pin "1") (pinfunction "1_1") (pintype "passive"))
      (node (ref "R79") (pin "1") (pinfunction "1_1") (pintype "passive"))
      (node (ref "TP4") (pin "1") (pinfunction "1_1") (pintype "passive"))
    )
    (net (code "6") (name "/DGATE_2_3S") (class "Default")
      (node (ref "J4") (pin "3") (pinfunction "3_3") (pintype "passive"))
      (node (ref "R73") (pin "1") (pinfunction "1_1") (pintype "passive"))
      (node (ref "R75") (pin "1") (pinfunction "1_1") (pintype "passive"))
      (node (ref "TP3") (pin "1") (pinfunction "1_1") (pintype "passive"))
    )
    (net (code "7") (name "/FAULT1_S") (class "Default")
      (node (ref "R62") (pin "1") (pinfunction "1_1") (pintype "passive"))
      (node (ref "S1") (pin "46") (pinfunction "~{FAULT}_46") (pintype "passive"))
    )
    (net (code "8") (name "/FAULT2_S") (class "Default")
      (node (ref "R64") (pin "1") (pinfunction "1_1") (pintype "passive"))
      (node (ref "S2") (pin "46") (pinfunction "~{FAULT}_46") (pintype "passive"))
    )
    (net (code "9") (name "/FAULT3_S") (class "Default")
      (node (ref "R63") (pin "1") (pinfunction "1_1") (pintype "passive"))
      (node (ref "S3") (pin "46") (pinfunction "~{FAULT}_46") (pintype "passive"))
    )
    (net (code "10") (name "/FAULT4_S") (class "Default")
      (node (ref "R66") (pin "1") (pinfunction "1_1") (pintype "passive"))
      (node (ref "S4") (pin "46") (pinfunction "~{FAULT}_46") (pintype "passive"))
    )
    (net (code "11") (name "/FLYBACK_IN") (class "Default")
      (node (ref "PS5") (pin "23") (pinfunction "+VIN_1_23") (pintype "passive"))
      (node (ref "PS5") (pin "24") (pinfunction "+VIN_2_24") (pintype "passive"))
      (node (ref "PS6") (pin "23") (pinfunction "+VIN_1_23") (pintype "passive"))
      (node (ref "PS6") (pin "24") (pinfunction "+VIN_2_24") (pintype "passive"))
      (node (ref "PS7") (pin "1") (pinfunction "+VIN_1") (pintype "passive"))
      (node (ref "PS8") (pin "1") (pinfunction "+VIN_1") (pintype "passive"))
    )
    (net (code "12") (name "/GATE_1S") (class "Default")
      (node (ref "C127") (pin "2") (pinfunction "2_2") (pintype "passive"))
      (node (ref "C93") (pin "1") (pinfunction "1_1") (pintype "passive"))
      (node (ref "R78") (pin "1") (pinfunction "1_1") (pintype "passive"))
      (node (ref "S1") (pin "45") (pinfunction "IN_45") (pintype "passive"))
    )
    (net (code "13") (name "/GATE_2S") (class "Default")
      (node (ref "C112") (pin "2") (pinfunction "2_2") (pintype "passive"))
      (node (ref "C123") (pin "2") (pinfunction "2_2") (pintype "passive"))
      (node (ref "R74") (pin "1") (pinfunction "1_1") (pintype "passive"))
      (node (ref "S2") (pin "45") (pinfunction "IN_45") (pintype "passive"))
    )
    (net (code "14") (name "/GATE_3S") (class "Default")
      (node (ref "C125") (pin "2") (pinfunction "2_2") (pintype "passive"))
      (node (ref "C97") (pin "2") (pinfunction "2_2") (pintype "passive"))
      (node (ref "R76") (pin "1") (pinfunction "1_1") (pintype "passive"))
      (node (ref "S3") (pin "45") (pinfunction "IN_45") (pintype "passive"))
    )
    (net (code "15") (name "/GATE_4S") (class "Default")
      (node (ref "C117") (pin "2") (pinfunction "2_2") (pintype "passive"))
      (node (ref "C129") (pin "2") (pinfunction "2_2") (pintype "passive"))
      (node (ref "R80") (pin "1") (pinfunction "1_1") (pintype "passive"))
      (node (ref "S4") (pin "45") (pinfunction "IN_45") (pintype "passive"))
    )
    (net (code "16") (name "/LDO_5V1S") (class "Default")
      (node (ref "C94") (pin "1") (pinfunction "1_1") (pintype "passive"))
      (node (ref "ISO7") (pin "8") (pinfunction "VDDB_8") (pintype "passive"))
      (node (ref "S1") (pin "51") (pinfunction "LDO5V_51") (pintype "passive"))
    )
    (net (code "17") (name "/LDO_5V2S") (class "Default")
      (node (ref "C113") (pin "2") (pinfunction "2_2") (pintype "passive"))
      (node (ref "ISO8") (pin "8") (pinfunction "VDDB_8") (pintype "passive"))
      (node (ref "S2") (pin "51") (pinfunction "LDO5V_51") (pintype "passive"))
    )
    (net (code "18") (name "/LDO_5V3S") (class "Default")
      (node (ref "C98") (pin "2") (pinfunction "2_2") (pintype "passive"))
      (node (ref "ISO9") (pin "8") (pinfunction "VDDB_8") (pintype "passive"))
      (node (ref "S3") (pin "51") (pinfunction "LDO5V_51") (pintype "passive"))
    )
    (net (code "19") (name "/SW_SL") (class "Default")
      (node (ref "C100") (pin "2") (pinfunction "2_2") (pintype "passive"))
      (node (ref "C127") (pin "1") (pinfunction "1_1") (pintype "passive"))
      (node (ref "C93") (pin "2") (pinfunction "2_2") (pintype "passive"))
      (node (ref "C94") (pin "2") (pinfunction "2_2") (pintype "passive"))
      (node (ref "C95") (pin "2") (pinfunction "2_2") (pintype "passive"))
      (node (ref "IC6") (pin "3") (pinfunction "K_3") (pintype "passive"))
      (node (ref "ISO7") (pin "5") (pinfunction "GNDB_5") (pintype "passive"))
      (node (ref "L6") (pin "2") (pinfunction "2_2") (pintype "passive"))
      (node (ref "PS5") (pin "11") (pinfunction "0V_1_11") (pintype "passive"))
      (node (ref "PS5") (pin "12") (pinfunction "0V_2_12") (pintype "passive"))
      (node (ref "PS5") (pin "13") (pinfunction "0V_3_13") (pintype "passive"))
      (node (ref "PS5") (pin "14") (pinfunction "0V_4_14") (pintype "passive"))
      (node (ref "R67") (pin "1") (pinfunction "1_1") (pintype "passive"))
      (node (ref "S1") (pin "18") (pinfunction "SOURCE_1_18") (pintype "passive"))
      (node (ref "S1") (pin "19") (pinfunction "SOURCE_2_19") (pintype "passive"))
      (node (ref "S1") (pin "20") (pinfunction "SOURCE_3_20") (pintype "passive"))
      (node (ref "S1") (pin "21") (pinfunction "SOURCE_4_21") (pintype "passive"))
      (node (ref "S1") (pin "22") (pinfunction "SOURCE_5_22") (pintype "passive"))
      (node (ref "S1") (pin "23") (pinfunction "SOURCE_6_23") (pintype "passive"))
      (node (ref "S1") (pin "24") (pinfunction "SOURCE_7_24") (pintype "passive"))
      (node (ref "S1") (pin "25") (pinfunction "SOURCE_8_25") (pintype "passive"))
      (node (ref "S1") (pin "26") (pinfunction "SOURCE_9_26") (pintype "passive"))
      (node (ref "S1") (pin "28") (pinfunction "SOURCE_10_28") (pintype "passive"))
      (node (ref "S1") (pin "29") (pinfunction "SOURCE_11_29") (pintype "passive"))
      (node (ref "S1") (pin "30") (pinfunction "SOURCE_12_30") (pintype "passive"))
      (node (ref "S1") (pin "31") (pinfunction "SOURCE_13_31") (pintype "passive"))
      (node (ref "S1") (pin "32") (pinfunction "SOURCE_14_32") (pintype "passive"))
      (node (ref "S1") (pin "33") (pinfunction "SOURCE_15_33") (pintype "passive"))
      (node (ref "S1") (pin "34") (pinfunction "SOURCE_16_34") (pintype "passive"))
      (node (ref "S1") (pin "35") (pinfunction "SOURCE_17_35") (pintype "passive"))
      (node (ref "S1") (pin "36") (pinfunction "SOURCE_18_36") (pintype "passive"))
      (node (ref "S1") (pin "37") (pinfunction "SOURCE_19_37") (pintype "passive"))
      (node (ref "S1") (pin "38") (pinfunction "SOURCE_20_38") (pintype "passive"))
      (node (ref "S1") (pin "39") (pinfunction "SOURCE_21_39") (pintype "passive"))
      (node (ref "S2") (pin "10") (pinfunction "DRAIN_9_10") (pintype "passive"))
      (node (ref "S2") (pin "11") (pinfunction "DRAIN_10_11") (pintype "passive"))
      (node (ref "S2") (pin "12") (pinfunction "DRAIN_11_12") (pintype "passive"))
      (node (ref "S2") (pin "13") (pinfunction "DRAIN_12_13") (pintype "passive"))
      (node (ref "S2") (pin "14") (pinfunction "DRAIN_13_14") (pintype "passive"))
      (node (ref "S2") (pin "15") (pinfunction "DRAIN_14_15") (pintype "passive"))
      (node (ref "S2") (pin "2") (pinfunction "DRAIN_1_2") (pintype "passive"))
      (node (ref "S2") (pin "3") (pinfunction "DRAIN_2_3") (pintype "passive"))
      (node (ref "S2") (pin "4") (pinfunction "DRAIN_3_4") (pintype "passive"))
      (node (ref "S2") (pin "5") (pinfunction "DRAIN_4_5") (pintype "passive"))
      (node (ref "S2") (pin "6") (pinfunction "DRAIN_5_6") (pintype "passive"))
      (node (ref "S2") (pin "7") (pinfunction "DRAIN_6_7") (pintype "passive"))
      (node (ref "S2") (pin "8") (pinfunction "DRAIN_7_8") (pintype "passive"))
      (node (ref "S2") (pin "9") (pinfunction "DRAIN_8_9") (pintype "passive"))
      (node (ref "TP16") (pin "1") (pinfunction "1_1") (pintype "passive"))
    )
    (net (code "20") (name "/SW_SR") (class "Default")
      (node (ref "C125") (pin "1") (pinfunction "1_1") (pintype "passive"))
      (node (ref "C96") (pin "1") (pinfunction "1_1") (pintype "passive"))
      (node (ref "C97") (pin "1") (pinfunction "1_1") (pintype "passive"))
      (node (ref "C98") (pin "1") (pinfunction "1_1") (pintype "passive"))
      (node (ref "C99") (pin "1") (pinfunction "1_1") (pintype "passive"))
      (node (ref "IC7") (pin "3") (pinfunction "K_3") (pintype "passive"))
      (node (ref "ISO9") (pin "5") (pinfunction "GNDB_5") (pintype "passive"))
      (node (ref "L7") (pin "2") (pinfunction "2_2") (pintype "passive"))
      (node (ref "PS6") (pin "11") (pinfunction "0V_1_11") (pintype "passive"))
      (node (ref "PS6") (pin "12") (pinfunction "0V_2_12") (pintype "passive"))
      (node (ref "PS6") (pin "13") (pinfunction "0V_3_13") (pintype "passive"))
      (node (ref "PS6") (pin "14") (pinfunction "0V_4_14") (pintype "passive"))
      (node (ref "R68") (pin "1") (pinfunction "1_1") (pintype "passive"))
      (node (ref "S3") (pin "18") (pinfunction "SOURCE_1_18") (pintype "passive"))
      (node (ref "S3") (pin "19") (pinfunction "SOURCE_2_19") (pintype "passive"))
      (node (ref "S3") (pin "20") (pinfunction "SOURCE_3_20") (pintype "passive"))
      (node (ref "S3") (pin "21") (pinfunction "SOURCE_4_21") (pintype "passive"))
      (node (ref "S3") (pin "22") (pinfunction "SOURCE_5_22") (pintype "passive"))
      (node (ref "S3") (pin "23") (pinfunction "SOURCE_6_23") (pintype "passive"))
      (node (ref "S3") (pin "24") (pinfunction "SOURCE_7_24") (pintype "passive"))
      (node (ref "S3") (pin "25") (pinfunction "SOURCE_8_25") (pintype "passive"))
      (node (ref "S3") (pin "26") (pinfunction "SOURCE_9_26") (pintype "passive"))
      (node (ref "S3") (pin "28") (pinfunction "SOURCE_10_28") (pintype "passive"))
      (node (ref "S3") (pin "29") (pinfunction "SOURCE_11_29") (pintype "passive"))
      (node (ref "S3") (pin "30") (pinfunction "SOURCE_12_30") (pintype "passive"))
      (node (ref "S3") (pin "31") (pinfunction "SOURCE_13_31") (pintype "passive"))
      (node (ref "S3") (pin "32") (pinfunction "SOURCE_14_32") (pintype "passive"))
      (node (ref "S3") (pin "33") (pinfunction "SOURCE_15_33") (pintype "passive"))
      (node (ref "S3") (pin "34") (pinfunction "SOURCE_16_34") (pintype "passive"))
      (node (ref "S3") (pin "35") (pinfunction "SOURCE_17_35") (pintype "passive"))
      (node (ref "S3") (pin "36") (pinfunction "SOURCE_18_36") (pintype "passive"))
      (node (ref "S3") (pin "37") (pinfunction "SOURCE_19_37") (pintype "passive"))
      (node (ref "S3") (pin "38") (pinfunction "SOURCE_20_38") (pintype "passive"))
      (node (ref "S3") (pin "39") (pinfunction "SOURCE_21_39") (pintype "passive"))
      (node (ref "S4") (pin "10") (pinfunction "DRAIN_9_10") (pintype "passive"))
      (node (ref "S4") (pin "11") (pinfunction "DRAIN_10_11") (pintype "passive"))
      (node (ref "S4") (pin "12") (pinfunction "DRAIN_11_12") (pintype "passive"))
      (node (ref "S4") (pin "13") (pinfunction "DRAIN_12_13") (pintype "passive"))
      (node (ref "S4") (pin "14") (pinfunction "DRAIN_13_14") (pintype "passive"))
      (node (ref "S4") (pin "15") (pinfunction "DRAIN_14_15") (pintype "passive"))
      (node (ref "S4") (pin "2") (pinfunction "DRAIN_1_2") (pintype "passive"))
      (node (ref "S4") (pin "3") (pinfunction "DRAIN_2_3") (pintype "passive"))
      (node (ref "S4") (pin "4") (pinfunction "DRAIN_3_4") (pintype "passive"))
      (node (ref "S4") (pin "5") (pinfunction "DRAIN_4_5") (pintype "passive"))
      (node (ref "S4") (pin "6") (pinfunction "DRAIN_5_6") (pintype "passive"))
      (node (ref "S4") (pin "7") (pinfunction "DRAIN_6_7") (pintype "passive"))
      (node (ref "S4") (pin "8") (pinfunction "DRAIN_7_8") (pintype "passive"))
      (node (ref "S4") (pin "9") (pinfunction "DRAIN_8_9") (pintype "passive"))
      (node (ref "TP17") (pin "1") (pinfunction "1_1") (pintype "passive"))
    )
    (net (code "21") (name "DGND") (class "Default")
      (node (ref "C122") (pin "2") (pinfunction "2_2") (pintype "passive"))
      (node (ref "C124") (pin "2") (pinfunction "2_2") (pintype "passive"))
      (node (ref "C126") (pin "2") (pinfunction "2_2") (pintype "passive"))
      (node (ref "C128") (pin "2") (pinfunction "2_2") (pintype "passive"))
      (node (ref "IC6") (pin "4") (pinfunction "GND_4") (pintype "passive"))
      (node (ref "IC7") (pin "4") (pinfunction "GND_4") (pintype "passive"))
      (node (ref "IC8") (pin "4") (pinfunction "GND_4") (pintype "passive"))
      (node (ref "IC9") (pin "4") (pinfunction "GND_4") (pintype "passive"))
      (node (ref "ISO7") (pin "4") (pinfunction "GNDA_4") (pintype "passive"))
      (node (ref "ISO8") (pin "4") (pinfunction "GNDA_4") (pintype "passive"))
      (node (ref "ISO9") (pin "4") (pinfunction "GNDA_4") (pintype "passive"))
      (node (ref "J4") (pin "1") (pinfunction "1_1") (pintype "passive"))
      (node (ref "J4") (pin "6") (pinfunction "6_6") (pintype "passive"))
      (node (ref "PS5") (pin "1") (pinfunction "-VIN_1_1") (pintype "passive"))
      (node (ref "PS5") (pin "2") (pinfunction "-VIN_2_2") (pintype "passive"))
      (node (ref "PS6") (pin "1") (pinfunction "-VIN_1_1") (pintype "passive"))
      (node (ref "PS6") (pin "2") (pinfunction "-VIN_2_2") (pintype "passive"))
      (node (ref "PS7") (pin "11") (pinfunction "-VIN_2_11") (pintype "passive"))
      (node (ref "PS7") (pin "2") (pinfunction "-VIN_1_2") (pintype "passive"))
      (node (ref "PS8") (pin "11") (pinfunction "-VIN_2_11") (pintype "passive"))
      (node (ref "PS8") (pin "2") (pinfunction "-VIN_1_2") (pintype "passive"))
      (node (ref "R65") (pin "1") (pinfunction "1_1") (pintype "passive"))
    )
    (net (code "22") (name "Net-(IC6-A)") (class "Default")
      (node (ref "IC6") (pin "1") (pinfunction "A_1") (pintype "passive"))
      (node (ref "R62") (pin "2") (pinfunction "2_2") (pintype "passive"))
    )
    (net (code "23") (name "Net-(IC6-VO_(OUTPUT))") (class "Default")
      (node (ref "D8") (pin "1") (pinfunction "1_1") (pintype "passive"))
      (node (ref "IC6") (pin "5") (pinfunction "VO_(OUTPUT)_5") (pintype "passive"))
    )
    (net (code "24") (name "Net-(IC7-A)") (class "Default")
      (node (ref "IC7") (pin "1") (pinfunction "A_1") (pintype "passive"))
      (node (ref "R63") (pin "2") (pinfunction "2_2") (pintype "passive"))
    )
    (net (code "25") (name "Net-(IC7-VO_(OUTPUT))") (class "Default")
      (node (ref "D9") (pin "1") (pinfunction "1_1") (pintype "passive"))
      (node (ref "IC7") (pin "5") (pinfunction "VO_(OUTPUT)_5") (pintype "passive"))
    )
    (net (code "26") (name "Net-(IC8-A)") (class "Default")
      (node (ref "IC8") (pin "1") (pinfunction "A_1") (pintype "passive"))
      (node (ref "R64") (pin "2") (pinfunction "2_2") (pintype "passive"))
    )
    (net (code "27") (name "Net-(IC8-VO_(OUTPUT))") (class "Default")
      (node (ref "D10") (pin "1") (pinfunction "1_1") (pintype "passive"))
      (node (ref "IC8") (pin "5") (pinfunction "VO_(OUTPUT)_5") (pintype "passive"))
    )
    (net (code "28") (name "Net-(IC9-A)") (class "Default")
      (node (ref "IC9") (pin "1") (pinfunction "A_1") (pintype "passive"))
      (node (ref "R66") (pin "2") (pinfunction "2_2") (pintype "passive"))
    )
    (net (code "29") (name "Net-(IC9-VO_(OUTPUT))") (class "Default")
      (node (ref "D11") (pin "1") (pinfunction "1_1") (pintype "passive"))
      (node (ref "IC9") (pin "5") (pinfunction "VO_(OUTPUT)_5") (pintype "passive"))
    )
    (net (code "30") (name "Net-(ISO7-IN2)") (class "Default")
      (node (ref "C126") (pin "1") (pinfunction "1_1") (pintype "passive"))
      (node (ref "ISO7") (pin "3") (pinfunction "IN2_3") (pintype "passive"))
      (node (ref "R77") (pin "2") (pinfunction "2_2") (pintype "passive"))
    )
    (net (code "31") (name "Net-(ISO7-OUT2)") (class "Default")
      (node (ref "ISO7") (pin "6") (pinfunction "OUT2_6") (pintype "passive"))
      (node (ref "R78") (pin "2") (pinfunction "2_2") (pintype "passive"))
    )
    (net (code "32") (name "Net-(ISO8-IN1)") (class "Default")
      (node (ref "C122") (pin "1") (pinfunction "1_1") (pintype "passive"))
      (node (ref "ISO8") (pin "2") (pinfunction "IN1_2") (pintype "passive"))
      (node (ref "R73") (pin "2") (pinfunction "2_2") (pintype "passive"))
    )
    (net (code "33") (name "Net-(ISO8-IN2)") (class "Default")
      (node (ref "C128") (pin "1") (pinfunction "1_1") (pintype "passive"))
      (node (ref "ISO8") (pin "3") (pinfunction "IN2_3") (pintype "passive"))
      (node (ref "R79") (pin "2") (pinfunction "2_2") (pintype "passive"))
    )
    (net (code "34") (name "Net-(ISO8-OUT1)") (class "Default")
      (node (ref "ISO8") (pin "7") (pinfunction "OUT1_7") (pintype "passive"))
      (node (ref "R74") (pin "2") (pinfunction "2_2") (pintype "passive"))
    )
    (net (code "35") (name "Net-(ISO8-OUT2)") (class "Default")
      (node (ref "ISO8") (pin "6") (pinfunction "OUT2_6") (pintype "passive"))
      (node (ref "R80") (pin "2") (pinfunction "2_2") (pintype "passive"))
    )
    (net (code "36") (name "Net-(ISO9-IN1)") (class "Default")
      (node (ref "C124") (pin "1") (pinfunction "1_1") (pintype "passive"))
      (node (ref "ISO9") (pin "2") (pinfunction "IN1_2") (pintype "passive"))
      (node (ref "R75") (pin "2") (pinfunction "2_2") (pintype "passive"))
    )
    (net (code "37") (name "Net-(ISO9-OUT1)") (class "Default")
      (node (ref "ISO9") (pin "7") (pinfunction "OUT1_7") (pintype "passive"))
      (node (ref "R76") (pin "2") (pinfunction "2_2") (pintype "passive"))
    )
    (net (code "38") (name "Net-(PS5-+VOUT_1)") (class "Default")
      (node (ref "C100") (pin "1") (pinfunction "1_1") (pintype "passive"))
      (node (ref "PS5") (pin "15") (pinfunction "+VOUT_1_15") (pintype "passive"))
      (node (ref "PS5") (pin "16") (pinfunction "+VOUT_2_16") (pintype "passive"))
      (node (ref "S1") (pin "44") (pinfunction "VDD_44") (pintype "passive"))
    )
    (net (code "39") (name "Net-(PS6-+VOUT_1)") (class "Default")
      (node (ref "C96") (pin "2") (pinfunction "2_2") (pintype "passive"))
      (node (ref "PS6") (pin "15") (pinfunction "+VOUT_1_15") (pintype "passive"))
      (node (ref "PS6") (pin "16") (pinfunction "+VOUT_2_16") (pintype "passive"))
      (node (ref "S3") (pin "44") (pinfunction "VDD_44") (pintype "passive"))
    )
    (net (code "40") (name "Net-(PS7-+VOUT)") (class "Default")
      (node (ref "C116") (pin "2") (pinfunction "2_2") (pintype "passive"))
      (node (ref "PS7") (pin "6") (pinfunction "+VOUT_6") (pintype "passive"))
      (node (ref "S4") (pin "44") (pinfunction "VDD_44") (pintype "passive"))
    )
    (net (code "41") (name "Net-(PS8-+VOUT)") (class "Default")
      (node (ref "C111") (pin "1") (pinfunction "1_1") (pintype "passive"))
      (node (ref "PS8") (pin "6") (pinfunction "+VOUT_6") (pintype "passive"))
      (node (ref "S2") (pin "44") (pinfunction "VDD_44") (pintype "passive"))
    )
    (net (code "42") (name "Net-(S1-BBSW)") (class "Default")
      (node (ref "L6") (pin "1") (pinfunction "1_1") (pintype "passive"))
      (node (ref "S1") (pin "42") (pinfunction "BBSW_42") (pintype "passive"))
    )
    (net (code "43") (name "Net-(S1-RDRV)") (class "Default")
      (node (ref "R67") (pin "2") (pinfunction "2_2") (pintype "passive"))
      (node (ref "S1") (pin "50") (pinfunction "RDRV_50") (pintype "passive"))
    )
    (net (code "44") (name "Net-(S1-VNEG_1)") (class "Default")
      (node (ref "C95") (pin "1") (pinfunction "1_1") (pintype "passive"))
      (node (ref "S1") (pin "40") (pinfunction "VNEG_1_40") (pintype "passive"))
      (node (ref "S1") (pin "41") (pinfunction "VNEG_2_41") (pintype "passive"))
    )
    (net (code "45") (name "Net-(S2-BBSW)") (class "Default")
      (node (ref "L8") (pin "1") (pinfunction "1_1") (pintype "passive"))
      (node (ref "S2") (pin "42") (pinfunction "BBSW_42") (pintype "passive"))
    )
    (net (code "46") (name "Net-(S2-RDRV)") (class "Default")
      (node (ref "R69") (pin "2") (pinfunction "2_2") (pintype "passive"))
      (node (ref "S2") (pin "50") (pinfunction "RDRV_50") (pintype "passive"))
    )
    (net (code "47") (name "Net-(S2-VNEG_1)") (class "Default")
      (node (ref "C114") (pin "1") (pinfunction "1_1") (pintype "passive"))
      (node (ref "S2") (pin "40") (pinfunction "VNEG_1_40") (pintype "passive"))
      (node (ref "S2") (pin "41") (pinfunction "VNEG_2_41") (pintype "passive"))
    )
    (net (code "48") (name "Net-(S3-BBSW)") (class "Default")
      (node (ref "L7") (pin "1") (pinfunction "1_1") (pintype "passive"))
      (node (ref "S3") (pin "42") (pinfunction "BBSW_42") (pintype "passive"))
    )
    (net (code "49") (name "Net-(S3-RDRV)") (class "Default")
      (node (ref "R68") (pin "2") (pinfunction "2_2") (pintype "passive"))
      (node (ref "S3") (pin "50") (pinfunction "RDRV_50") (pintype "passive"))
    )
    (net (code "50") (name "Net-(S3-VNEG_1)") (class "Default")
      (node (ref "C99") (pin "2") (pinfunction "2_2") (pintype "passive"))
      (node (ref "S3") (pin "40") (pinfunction "VNEG_1_40") (pintype "passive"))
      (node (ref "S3") (pin "41") (pinfunction "VNEG_2_41") (pintype "passive"))
    )
    (net (code "51") (name "Net-(S4-BBSW)") (class "Default")
      (node (ref "L9") (pin "1") (pinfunction "1_1") (pintype "passive"))
      (node (ref "S4") (pin "42") (pinfunction "BBSW_42") (pintype "passive"))
    )
    (net (code "52") (name "Net-(S4-RDRV)") (class "Default")
      (node (ref "R70") (pin "2") (pinfunction "2_2") (pintype "passive"))
      (node (ref "S4") (pin "50") (pinfunction "RDRV_50") (pintype "passive"))
    )
    (net (code "53") (name "Net-(S4-VNEG_1)") (class "Default")
      (node (ref "C119") (pin "2") (pinfunction "2_2") (pintype "passive"))
      (node (ref "S4") (pin "40") (pinfunction "VNEG_1_40") (pintype "passive"))
      (node (ref "S4") (pin "41") (pinfunction "VNEG_2_41") (pintype "passive"))
    )
    (net (code "54") (name "SGND") (class "Default")
      (node (ref "C111") (pin "2") (pinfunction "2_2") (pintype "passive"))
      (node (ref "C112") (pin "1") (pinfunction "1_1") (pintype "passive"))
      (node (ref "C113") (pin "1") (pinfunction "1_1") (pintype "passive"))
      (node (ref "C114") (pin "2") (pinfunction "2_2") (pintype "passive"))
      (node (ref "C116") (pin "1") (pinfunction "1_1") (pintype "passive"))
      (node (ref "C117") (pin "1") (pinfunction "1_1") (pintype "passive"))
      (node (ref "C118") (pin "1") (pinfunction "1_1") (pintype "passive"))
      (node (ref "C119") (pin "1") (pinfunction "1_1") (pintype "passive"))
      (node (ref "C123") (pin "1") (pinfunction "1_1") (pintype "passive"))
      (node (ref "C129") (pin "1") (pinfunction "1_1") (pintype "passive"))
      (node (ref "IC8") (pin "3") (pinfunction "K_3") (pintype "passive"))
      (node (ref "IC9") (pin "3") (pinfunction "K_3") (pintype "passive"))
      (node (ref "ISO8") (pin "5") (pinfunction "GNDB_5") (pintype "passive"))
      (node (ref "L8") (pin "2") (pinfunction "2_2") (pintype "passive"))
      (node (ref "L9") (pin "2") (pinfunction "2_2") (pintype "passive"))
      (node (ref "PS7") (pin "5") (pinfunction "-VOUT_5") (pintype "passive"))
      (node (ref "PS8") (pin "5") (pinfunction "-VOUT_5") (pintype "passive"))
      (node (ref "R69") (pin "1") (pinfunction "1_1") (pintype "passive"))
      (node (ref "R70") (pin "1") (pinfunction "1_1") (pintype "passive"))
      (node (ref "S2") (pin "18") (pinfunction "SOURCE_1_18") (pintype "passive"))
      (node (ref "S2") (pin "19") (pinfunction "SOURCE_2_19") (pintype "passive"))
      (node (ref "S2") (pin "20") (pinfunction "SOURCE_3_20") (pintype "passive"))
      (node (ref "S2") (pin "21") (pinfunction "SOURCE_4_21") (pintype "passive"))
      (node (ref "S2") (pin "22") (pinfunction "SOURCE_5_22") (pintype "passive"))
      (node (ref "S2") (pin "23") (pinfunction "SOURCE_6_23") (pintype "passive"))
      (node (ref "S2") (pin "24") (pinfunction "SOURCE_7_24") (pintype "passive"))
      (node (ref "S2") (pin "25") (pinfunction "SOURCE_8_25") (pintype "passive"))
      (node (ref "S2") (pin "26") (pinfunction "SOURCE_9_26") (pintype "passive"))
      (node (ref "S2") (pin "28") (pinfunction "SOURCE_10_28") (pintype "passive"))
      (node (ref "S2") (pin "29") (pinfunction "SOURCE_11_29") (pintype "passive"))
      (node (ref "S2") (pin "30") (pinfunction "SOURCE_12_30") (pintype "passive"))
      (node (ref "S2") (pin "31") (pinfunction "SOURCE_13_31") (pintype "passive"))
      (node (ref "S2") (pin "32") (pinfunction "SOURCE_14_32") (pintype "passive"))
      (node (ref "S2") (pin "33") (pinfunction "SOURCE_15_33") (pintype "passive"))
      (node (ref "S2") (pin "34") (pinfunction "SOURCE_16_34") (pintype "passive"))
      (node (ref "S2") (pin "35") (pinfunction "SOURCE_17_35") (pintype "passive"))
      (node (ref "S2") (pin "36") (pinfunction "SOURCE_18_36") (pintype "passive"))
      (node (ref "S2") (pin "37") (pinfunction "SOURCE_19_37") (pintype "passive"))
      (node (ref "S2") (pin "38") (pinfunction "SOURCE_20_38") (pintype "passive"))
      (node (ref "S2") (pin "39") (pinfunction "SOURCE_21_39") (pintype "passive"))
      (node (ref "S4") (pin "18") (pinfunction "SOURCE_1_18") (pintype "passive"))
      (node (ref "S4") (pin "19") (pinfunction "SOURCE_2_19") (pintype "passive"))
      (node (ref "S4") (pin "20") (pinfunction "SOURCE_3_20") (pintype "passive"))
      (node (ref "S4") (pin "21") (pinfunction "SOURCE_4_21") (pintype "passive"))
      (node (ref "S4") (pin "22") (pinfunction "SOURCE_5_22") (pintype "passive"))
      (node (ref "S4") (pin "23") (pinfunction "SOURCE_6_23") (pintype "passive"))
      (node (ref "S4") (pin "24") (pinfunction "SOURCE_7_24") (pintype "passive"))
      (node (ref "S4") (pin "25") (pinfunction "SOURCE_8_25") (pintype "passive"))
      (node (ref "S4") (pin "26") (pinfunction "SOURCE_9_26") (pintype "passive"))
      (node (ref "S4") (pin "28") (pinfunction "SOURCE_10_28") (pintype "passive"))
      (node (ref "S4") (pin "29") (pinfunction "SOURCE_11_29") (pintype "passive"))
      (node (ref "S4") (pin "30") (pinfunction "SOURCE_12_30") (pintype "passive"))
      (node (ref "S4") (pin "31") (pinfunction "SOURCE_13_31") (pintype "passive"))
      (node (ref "S4") (pin "32") (pinfunction "SOURCE_14_32") (pintype "passive"))
      (node (ref "S4") (pin "33") (pinfunction "SOURCE_15_33") (pintype "passive"))
      (node (ref "S4") (pin "34") (pinfunction "SOURCE_16_34") (pintype "passive"))
      (node (ref "S4") (pin "35") (pinfunction "SOURCE_17_35") (pintype "passive"))
      (node (ref "S4") (pin "36") (pinfunction "SOURCE_18_36") (pintype "passive"))
      (node (ref "S4") (pin "37") (pinfunction "SOURCE_19_37") (pintype "passive"))
      (node (ref "S4") (pin "38") (pinfunction "SOURCE_20_38") (pintype "passive"))
      (node (ref "S4") (pin "39") (pinfunction "SOURCE_21_39") (pintype "passive"))
    )
    (net (code "55") (name "unconnected-(IC6-NO_PIN-Pad2)") (class "Default")
      (node (ref "IC6") (pin "2") (pinfunction "NO_PIN_2") (pintype "passive"))
    )
    (net (code "56") (name "unconnected-(IC7-NO_PIN-Pad2)") (class "Default")
      (node (ref "IC7") (pin "2") (pinfunction "NO_PIN_2") (pintype "passive"))
    )
    (net (code "57") (name "unconnected-(IC8-NO_PIN-Pad2)") (class "Default")
      (node (ref "IC8") (pin "2") (pinfunction "NO_PIN_2") (pintype "passive"))
    )
    (net (code "58") (name "unconnected-(IC9-NO_PIN-Pad2)") (class "Default")
      (node (ref "IC9") (pin "2") (pinfunction "NO_PIN_2") (pintype "passive"))
    )
    (net (code "59") (name "unconnected-(ISO7-IN1-Pad7)") (class "Default")
      (node (ref "ISO7") (pin "7") (pinfunction "IN1_7") (pintype "passive"))
    )
    (net (code "60") (name "unconnected-(ISO7-OUT1-Pad2)") (class "Default")
      (node (ref "ISO7") (pin "2") (pinfunction "OUT1_2") (pintype "passive"))
    )
    (net (code "61") (name "unconnected-(ISO9-IN2-Pad3)") (class "Default")
      (node (ref "ISO9") (pin "3") (pinfunction "IN2_3") (pintype "passive"))
    )
    (net (code "62") (name "unconnected-(ISO9-OUT2-Pad6)") (class "Default")
      (node (ref "ISO9") (pin "6") (pinfunction "OUT2_6") (pintype "passive"))
    )
    (net (code "63") (name "unconnected-(J4-MP1-Pad7)") (class "Default")
      (node (ref "J4") (pin "7") (pinfunction "MP1_7") (pintype "passive"))
    )
    (net (code "64") (name "unconnected-(J4-MP2-Pad8)") (class "Default")
      (node (ref "J4") (pin "8") (pinfunction "MP2_8") (pintype "passive"))
    )
    (net (code "65") (name "unconnected-(J4-MP3-Pad9)") (class "Default")
      (node (ref "J4") (pin "9") (pinfunction "MP3_9") (pintype "passive"))
    )
    (net (code "66") (name "unconnected-(J4-MP4-Pad10)") (class "Default")
      (node (ref "J4") (pin "10") (pinfunction "MP4_10") (pintype "passive"))
    )
    (net (code "67") (name "unconnected-(PS5--VOUT_1-Pad9)") (class "Default")
      (node (ref "PS5") (pin "9") (pinfunction "-VOUT_1_9") (pintype "passive"))
    )
    (net (code "68") (name "unconnected-(PS5--VOUT_2-Pad10)") (class "Default")
      (node (ref "PS5") (pin "10") (pinfunction "-VOUT_2_10") (pintype "passive"))
    )
    (net (code "69") (name "unconnected-(PS6--VOUT_1-Pad9)") (class "Default")
      (node (ref "PS6") (pin "9") (pinfunction "-VOUT_1_9") (pintype "passive"))
    )
    (net (code "70") (name "unconnected-(PS6--VOUT_2-Pad10)") (class "Default")
      (node (ref "PS6") (pin "10") (pinfunction "-VOUT_2_10") (pintype "passive"))
    )
    (net (code "71") (name "unconnected-(PS7-NC_1-Pad7)") (class "Default")
      (node (ref "PS7") (pin "7") (pinfunction "NC_1_7") (pintype "passive"))
    )
    (net (code "72") (name "unconnected-(PS7-NC_2-Pad8)") (class "Default")
      (node (ref "PS7") (pin "8") (pinfunction "NC_2_8") (pintype "passive"))
    )
    (net (code "73") (name "unconnected-(PS7-NC_3-Pad12)") (class "Default")
      (node (ref "PS7") (pin "12") (pinfunction "NC_3_12") (pintype "passive"))
    )
    (net (code "74") (name "unconnected-(PS8-NC_1-Pad7)") (class "Default")
      (node (ref "PS8") (pin "7") (pinfunction "NC_1_7") (pintype "passive"))
    )
    (net (code "75") (name "unconnected-(PS8-NC_2-Pad8)") (class "Default")
      (node (ref "PS8") (pin "8") (pinfunction "NC_2_8") (pintype "passive"))
    )
    (net (code "76") (name "unconnected-(PS8-NC_3-Pad12)") (class "Default")
      (node (ref "PS8") (pin "12") (pinfunction "NC_3_12") (pintype "passive"))
    )
    (net (code "77") (name "unconnected-(S1-NC1_1-Pad1)") (class "Default")
      (node (ref "S1") (pin "1") (pinfunction "NC1_1_1") (pintype "passive"))
    )
    (net (code "78") (name "unconnected-(S1-NC1_2-Pad16)") (class "Default")
      (node (ref "S1") (pin "16") (pinfunction "NC1_2_16") (pintype "passive"))
    )
    (net (code "79") (name "unconnected-(S1-NC2_1-Pad17)") (class "Default")
      (node (ref "S1") (pin "17") (pinfunction "NC2_1_17") (pintype "passive"))
    )
    (net (code "80") (name "unconnected-(S1-NC2_2-Pad27)") (class "Default")
      (node (ref "S1") (pin "27") (pinfunction "NC2_2_27") (pintype "passive"))
    )
    (net (code "81") (name "unconnected-(S1-NC2_3-Pad43)") (class "Default")
      (node (ref "S1") (pin "43") (pinfunction "NC2_3_43") (pintype "passive"))
    )
    (net (code "82") (name "unconnected-(S1-NC2_4-Pad47)") (class "Default")
      (node (ref "S1") (pin "47") (pinfunction "NC2_4_47") (pintype "passive"))
    )
    (net (code "83") (name "unconnected-(S1-NC2_5-Pad52)") (class "Default")
      (node (ref "S1") (pin "52") (pinfunction "NC2_5_52") (pintype "passive"))
    )
    (net (code "84") (name "unconnected-(S1-TEMP-Pad49)") (class "Default")
      (node (ref "S1") (pin "49") (pinfunction "TEMP_49") (pintype "passive"))
    )
    (net (code "85") (name "unconnected-(S1-~{OC}-Pad48)") (class "Default")
      (node (ref "S1") (pin "48") (pinfunction "~{OC}_48") (pintype "passive"))
    )
    (net (code "86") (name "unconnected-(S2-NC1_1-Pad1)") (class "Default")
      (node (ref "S2") (pin "1") (pinfunction "NC1_1_1") (pintype "passive"))
    )
    (net (code "87") (name "unconnected-(S2-NC1_2-Pad16)") (class "Default")
      (node (ref "S2") (pin "16") (pinfunction "NC1_2_16") (pintype "passive"))
    )
    (net (code "88") (name "unconnected-(S2-NC2_1-Pad17)") (class "Default")
      (node (ref "S2") (pin "17") (pinfunction "NC2_1_17") (pintype "passive"))
    )
    (net (code "89") (name "unconnected-(S2-NC2_2-Pad27)") (class "Default")
      (node (ref "S2") (pin "27") (pinfunction "NC2_2_27") (pintype "passive"))
    )
    (net (code "90") (name "unconnected-(S2-NC2_3-Pad43)") (class "Default")
      (node (ref "S2") (pin "43") (pinfunction "NC2_3_43") (pintype "passive"))
    )
    (net (code "91") (name "unconnected-(S2-NC2_4-Pad47)") (class "Default")
      (node (ref "S2") (pin "47") (pinfunction "NC2_4_47") (pintype "passive"))
    )
    (net (code "92") (name "unconnected-(S2-NC2_5-Pad52)") (class "Default")
      (node (ref "S2") (pin "52") (pinfunction "NC2_5_52") (pintype "passive"))
    )
    (net (code "93") (name "unconnected-(S2-TEMP-Pad49)") (class "Default")
      (node (ref "S2") (pin "49") (pinfunction "TEMP_49") (pintype "passive"))
    )
    (net (code "94") (name "unconnected-(S2-~{OC}-Pad48)") (class "Default")
      (node (ref "S2") (pin "48") (pinfunction "~{OC}_48") (pintype "passive"))
    )
    (net (code "95") (name "unconnected-(S3-NC1_1-Pad1)") (class "Default")
      (node (ref "S3") (pin "1") (pinfunction "NC1_1_1") (pintype "passive"))
    )
    (net (code "96") (name "unconnected-(S3-NC1_2-Pad16)") (class "Default")
      (node (ref "S3") (pin "16") (pinfunction "NC1_2_16") (pintype "passive"))
    )
    (net (code "97") (name "unconnected-(S3-NC2_1-Pad17)") (class "Default")
      (node (ref "S3") (pin "17") (pinfunction "NC2_1_17") (pintype "passive"))
    )
    (net (code "98") (name "unconnected-(S3-NC2_2-Pad27)") (class "Default")
      (node (ref "S3") (pin "27") (pinfunction "NC2_2_27") (pintype "passive"))
    )
    (net (code "99") (name "unconnected-(S3-NC2_3-Pad43)") (class "Default")
      (node (ref "S3") (pin "43") (pinfunction "NC2_3_43") (pintype "passive"))
    )
    (net (code "100") (name "unconnected-(S3-NC2_4-Pad47)") (class "Default")
      (node (ref "S3") (pin "47") (pinfunction "NC2_4_47") (pintype "passive"))
    )
    (net (code "101") (name "unconnected-(S3-NC2_5-Pad52)") (class "Default")
      (node (ref "S3") (pin "52") (pinfunction "NC2_5_52") (pintype "passive"))
    )
    (net (code "102") (name "unconnected-(S3-TEMP-Pad49)") (class "Default")
      (node (ref "S3") (pin "49") (pinfunction "TEMP_49") (pintype "passive"))
    )
    (net (code "103") (name "unconnected-(S3-~{OC}-Pad48)") (class "Default")
      (node (ref "S3") (pin "48") (pinfunction "~{OC}_48") (pintype "passive"))
    )
    (net (code "104") (name "unconnected-(S4-NC1_1-Pad1)") (class "Default")
      (node (ref "S4") (pin "1") (pinfunction "NC1_1_1") (pintype "passive"))
    )
    (net (code "105") (name "unconnected-(S4-NC1_2-Pad16)") (class "Default")
      (node (ref "S4") (pin "16") (pinfunction "NC1_2_16") (pintype "passive"))
    )
    (net (code "106") (name "unconnected-(S4-NC2_1-Pad17)") (class "Default")
      (node (ref "S4") (pin "17") (pinfunction "NC2_1_17") (pintype "passive"))
    )
    (net (code "107") (name "unconnected-(S4-NC2_2-Pad27)") (class "Default")
      (node (ref "S4") (pin "27") (pinfunction "NC2_2_27") (pintype "passive"))
    )
    (net (code "108") (name "unconnected-(S4-NC2_3-Pad43)") (class "Default")
      (node (ref "S4") (pin "43") (pinfunction "NC2_3_43") (pintype "passive"))
    )
    (net (code "109") (name "unconnected-(S4-NC2_4-Pad47)") (class "Default")
      (node (ref "S4") (pin "47") (pinfunction "NC2_4_47") (pintype "passive"))
    )
    (net (code "110") (name "unconnected-(S4-NC2_5-Pad52)") (class "Default")
      (node (ref "S4") (pin "52") (pinfunction "NC2_5_52") (pintype "passive"))
    )
    (net (code "111") (name "unconnected-(S4-TEMP-Pad49)") (class "Default")
      (node (ref "S4") (pin "49") (pinfunction "TEMP_49") (pintype "passive"))
    )
    (net (code "112") (name "unconnected-(S4-~{OC}-Pad48)") (class "Default")
      (node (ref "S4") (pin "48") (pinfunction "~{OC}_48") (pintype "passive"))
    )
  )
)
